# ramanSpectrometer_electronic_controlBoar.net
KiCad netlist of a schematic drawn in EAGLE
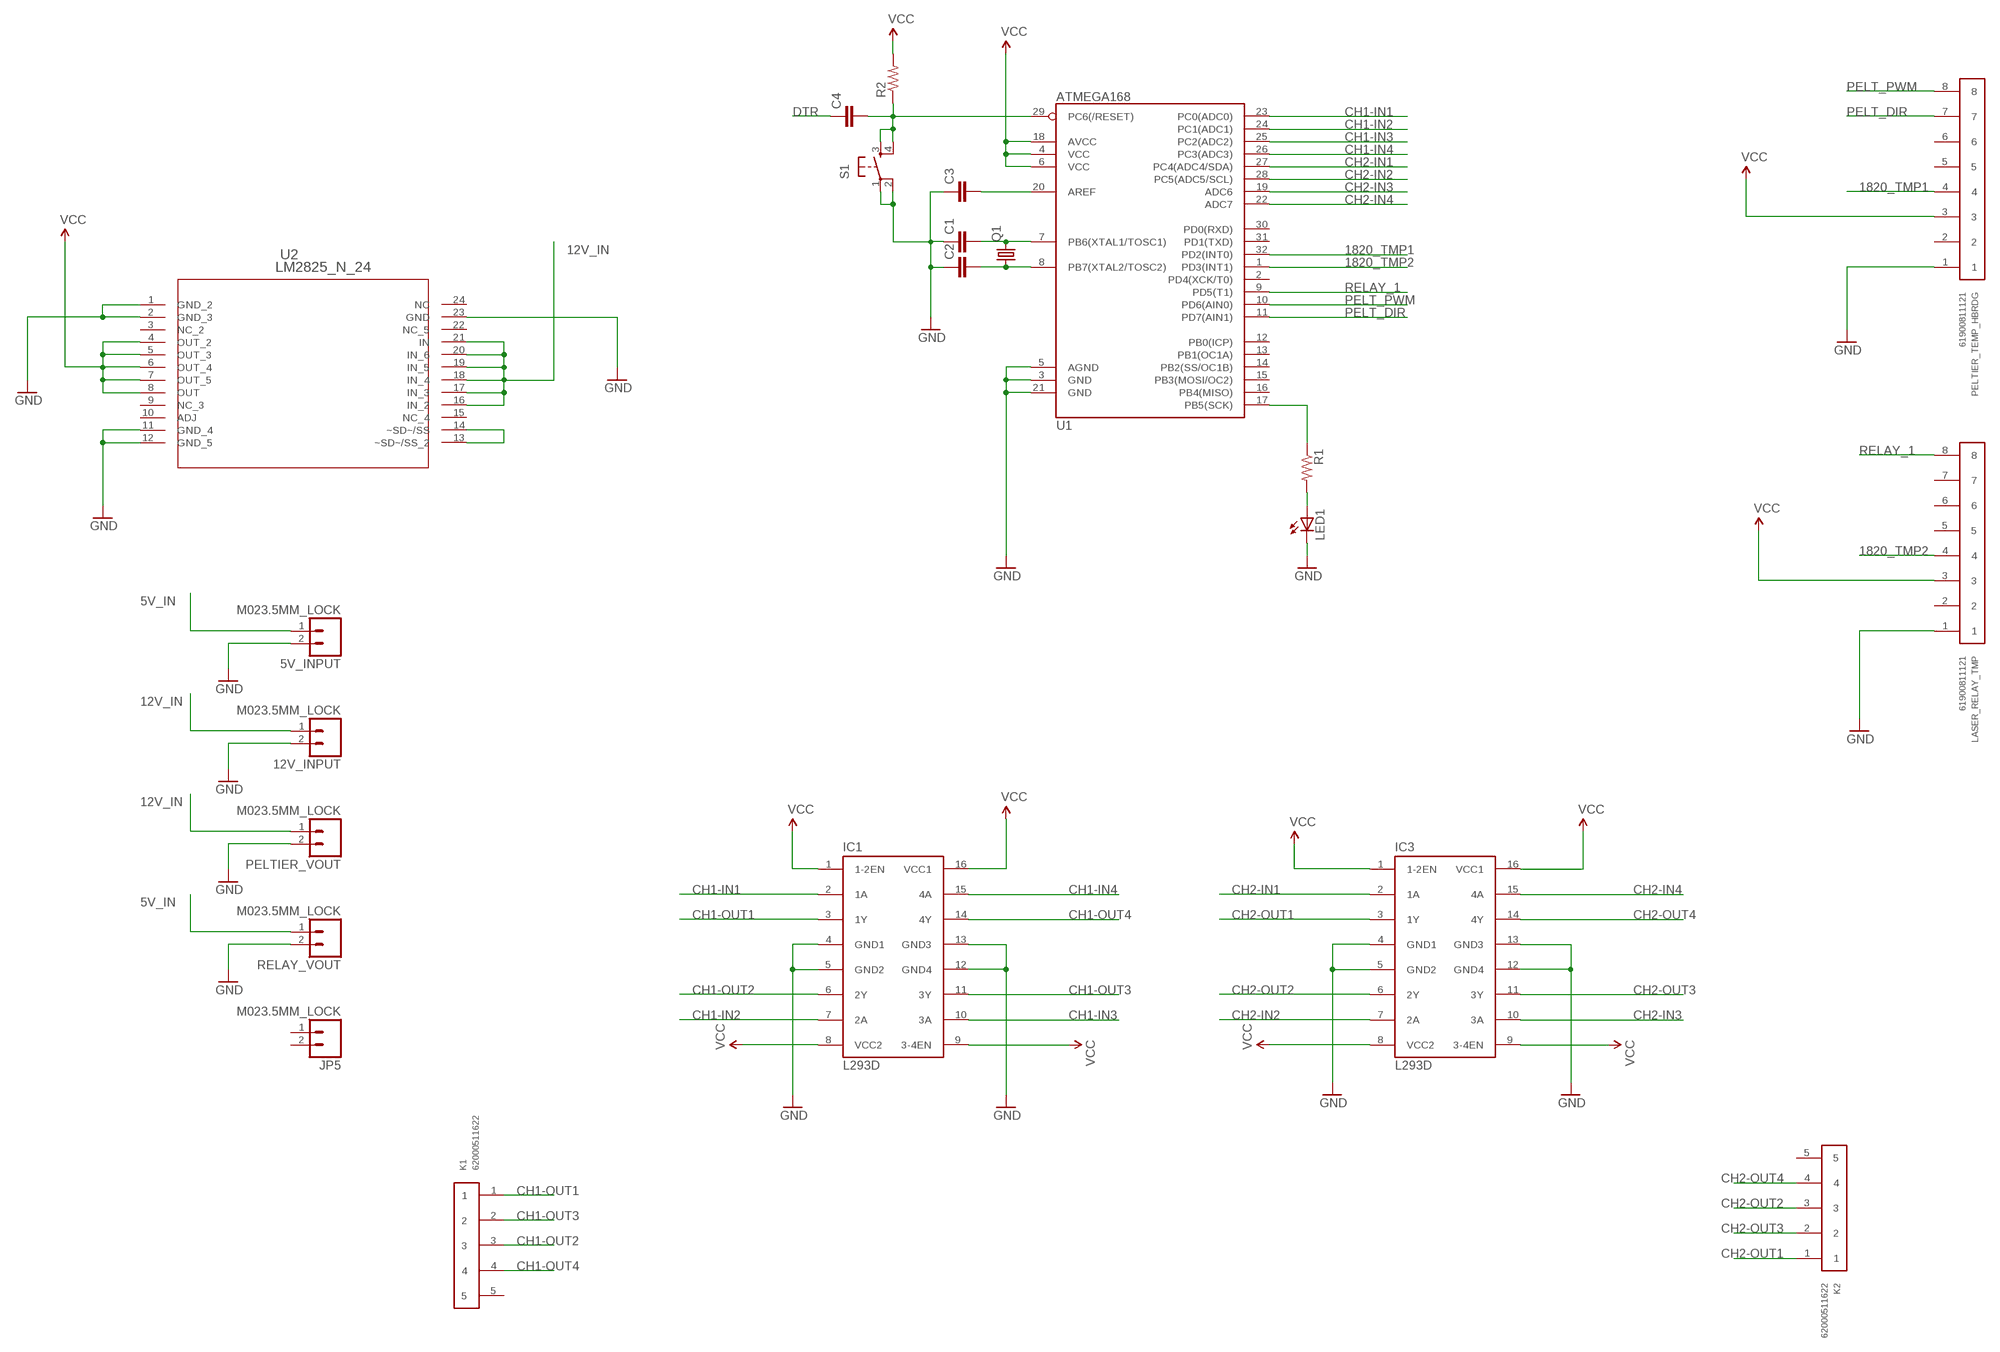
[diagram p0: schematic, sheet 1]

(export (version "E")
  (design (tool "Eeschema 10.0.6"))
  (components
    (comp (ref "5V_INPUT")
      (value "M023.5MM_LOCK")
      (footprint "eagle-import:SCREWTERMINAL-3.5MM-2_LOCK")
      (libsource (lib "eagle-import") (part "M023.5MM_LOCK"))
    )
    (comp (ref "12V_INPUT")
      (value "M023.5MM_LOCK")
      (footprint "eagle-import:SCREWTERMINAL-3.5MM-2_LOCK")
      (libsource (lib "eagle-import") (part "M023.5MM_LOCK"))
    )
    (comp (ref "C1")
      (value "CAP1206")
      (footprint "eagle-import:1206")
      (libsource (lib "eagle-import") (part "CAP1206"))
    )
    (comp (ref "C2")
      (value "CAP1206")
      (footprint "eagle-import:1206")
      (libsource (lib "eagle-import") (part "CAP1206"))
    )
    (comp (ref "C3")
      (value "CAP1210")
      (footprint "eagle-import:1210")
      (libsource (lib "eagle-import") (part "CAP1210"))
    )
    (comp (ref "C4")
      (value "CAP1210")
      (footprint "eagle-import:1210")
      (libsource (lib "eagle-import") (part "CAP1210"))
    )
    (comp (ref "IC1")
      (value "L293D")
      (footprint "eagle-import:DIL16")
      (libsource (lib "eagle-import") (part "L293D"))
    )
    (comp (ref "IC3")
      (value "L293D")
      (footprint "eagle-import:DIL16")
      (libsource (lib "eagle-import") (part "L293D"))
    )
    (comp (ref "JP5")
      (value "M023.5MM_LOCK")
      (footprint "eagle-import:SCREWTERMINAL-3.5MM-2_LOCK")
      (libsource (lib "eagle-import") (part "M023.5MM_LOCK"))
    )
    (comp (ref "K1")
      (value "62000511622")
      (footprint "eagle-import:62000511622")
      (libsource (lib "eagle-import") (part "62000511622"))
    )
    (comp (ref "K2")
      (value "62000511622")
      (footprint "eagle-import:62000511622")
      (libsource (lib "eagle-import") (part "62000511622"))
    )
    (comp (ref "LASER_RELAY_TMP")
      (value "61900811121")
      (footprint "eagle-import:61900811121")
      (libsource (lib "eagle-import") (part "61900811121"))
    )
    (comp (ref "LED1")
      (value "LEDP-LCC-2")
      (footprint "eagle-import:P-LCC-2")
      (libsource (lib "eagle-import") (part "LEDP-LCC-2"))
    )
    (comp (ref "PELTIER_TEMP_HBRDG")
      (value "61900811121")
      (footprint "eagle-import:61900811121")
      (libsource (lib "eagle-import") (part "61900811121"))
    )
    (comp (ref "PELTIER_VOUT")
      (value "M023.5MM_LOCK")
      (footprint "eagle-import:SCREWTERMINAL-3.5MM-2_LOCK")
      (libsource (lib "eagle-import") (part "M023.5MM_LOCK"))
    )
    (comp (ref "Q1")
      (value "CRYSTALSM49")
      (footprint "eagle-import:SM49")
      (libsource (lib "eagle-import") (part "CRYSTALSM49"))
    )
    (comp (ref "R1")
      (value "RESISTOR1206")
      (footprint "eagle-import:1206")
      (libsource (lib "eagle-import") (part "RESISTOR1206"))
    )
    (comp (ref "R2")
      (value "RESISTOR1206")
      (footprint "eagle-import:1206")
      (libsource (lib "eagle-import") (part "RESISTOR1206"))
    )
    (comp (ref "RELAY_VOUT")
      (value "M023.5MM_LOCK")
      (footprint "eagle-import:SCREWTERMINAL-3.5MM-2_LOCK")
      (libsource (lib "eagle-import") (part "M023.5MM_LOCK"))
    )
    (comp (ref "S1")
      (value "TAC_SWITCHSMD")
      (footprint "eagle-import:TACTILE_SWITCH_SMD")
      (libsource (lib "eagle-import") (part "TAC_SWITCHSMD"))
    )
    (comp (ref "U1")
      (value "ATMEGA168")
      (footprint "eagle-import:TQFP32-08")
      (libsource (lib "eagle-import") (part "ATMEGA168"))
    )
    (comp (ref "U2")
      (value "LM2825_N_24")
      (footprint "eagle-import:NA24F")
      (fields (field (name "PARTNUMBER") "LM2825HN-ADJ"))
      (libsource (lib "eagle-import") (part "LM2825_N_24"))
    )
  )
  (nets
    (net (code "1") (name "/5V_IN") (class "Default")
      (node (ref "5V_INPUT") (pin "1") (pinfunction "1_1") (pintype "passive"))
      (node (ref "RELAY_VOUT") (pin "1") (pinfunction "1_1") (pintype "passive"))
    )
    (net (code "2") (name "/12V_IN") (class "Default")
      (node (ref "12V_INPUT") (pin "1") (pinfunction "1_1") (pintype "passive"))
      (node (ref "PELTIER_VOUT") (pin "1") (pinfunction "1_1") (pintype "passive"))
      (node (ref "U2") (pin "16") (pinfunction "IN_2_16") (pintype "input"))
      (node (ref "U2") (pin "17") (pinfunction "IN_3_17") (pintype "input"))
      (node (ref "U2") (pin "18") (pinfunction "IN_4_18") (pintype "input"))
      (node (ref "U2") (pin "19") (pinfunction "IN_5_19") (pintype "input"))
      (node (ref "U2") (pin "20") (pinfunction "IN_6_20") (pintype "input"))
      (node (ref "U2") (pin "21") (pinfunction "IN_21") (pintype "input"))
    )
    (net (code "3") (name "/1820_TMP1") (class "Default")
      (node (ref "PELTIER_TEMP_HBRDG") (pin "4") (pinfunction "4_4") (pintype "bidirectional"))
      (node (ref "U1") (pin "32") (pinfunction "PD2(INT0)_32") (pintype "bidirectional"))
    )
    (net (code "4") (name "/1820_TMP2") (class "Default")
      (node (ref "LASER_RELAY_TMP") (pin "4") (pinfunction "4_4") (pintype "bidirectional"))
      (node (ref "U1") (pin "1") (pinfunction "PD3(INT1)_1") (pintype "bidirectional"))
    )
    (net (code "5") (name "/CH1-IN1") (class "Default")
      (node (ref "IC1") (pin "2") (pinfunction "1A_2") (pintype "input"))
      (node (ref "U1") (pin "23") (pinfunction "PC0(ADC0)_23") (pintype "bidirectional"))
    )
    (net (code "6") (name "/CH1-IN2") (class "Default")
      (node (ref "IC1") (pin "7") (pinfunction "2A_7") (pintype "input"))
      (node (ref "U1") (pin "24") (pinfunction "PC1(ADC1)_24") (pintype "bidirectional"))
    )
    (net (code "7") (name "/CH1-IN3") (class "Default")
      (node (ref "IC1") (pin "10") (pinfunction "3A_10") (pintype "input"))
      (node (ref "U1") (pin "25") (pinfunction "PC2(ADC2)_25") (pintype "bidirectional"))
    )
    (net (code "8") (name "/CH1-IN4") (class "Default")
      (node (ref "IC1") (pin "15") (pinfunction "4A_15") (pintype "input"))
      (node (ref "U1") (pin "26") (pinfunction "PC3(ADC3)_26") (pintype "bidirectional"))
    )
    (net (code "9") (name "/CH1-OUT1") (class "Default")
      (node (ref "IC1") (pin "3") (pinfunction "1Y_3") (pintype "output"))
      (node (ref "K1") (pin "1") (pinfunction "1_1") (pintype "bidirectional"))
    )
    (net (code "10") (name "/CH1-OUT2") (class "Default")
      (node (ref "IC1") (pin "6") (pinfunction "2Y_6") (pintype "output"))
      (node (ref "K1") (pin "3") (pinfunction "3_3") (pintype "bidirectional"))
    )
    (net (code "11") (name "/CH1-OUT3") (class "Default")
      (node (ref "IC1") (pin "11") (pinfunction "3Y_11") (pintype "output"))
      (node (ref "K1") (pin "2") (pinfunction "2_2") (pintype "bidirectional"))
    )
    (net (code "12") (name "/CH1-OUT4") (class "Default")
      (node (ref "IC1") (pin "14") (pinfunction "4Y_14") (pintype "output"))
      (node (ref "K1") (pin "4") (pinfunction "4_4") (pintype "bidirectional"))
    )
    (net (code "13") (name "/CH2-IN1") (class "Default")
      (node (ref "IC3") (pin "2") (pinfunction "1A_2") (pintype "input"))
      (node (ref "U1") (pin "27") (pinfunction "PC4(ADC4/SDA)_27") (pintype "bidirectional"))
    )
    (net (code "14") (name "/CH2-IN2") (class "Default")
      (node (ref "IC3") (pin "7") (pinfunction "2A_7") (pintype "input"))
      (node (ref "U1") (pin "28") (pinfunction "PC5(ADC5/SCL)_28") (pintype "bidirectional"))
    )
    (net (code "15") (name "/CH2-IN3") (class "Default")
      (node (ref "IC3") (pin "10") (pinfunction "3A_10") (pintype "input"))
      (node (ref "U1") (pin "19") (pinfunction "ADC6_19") (pintype "bidirectional"))
    )
    (net (code "16") (name "/CH2-IN4") (class "Default")
      (node (ref "IC3") (pin "15") (pinfunction "4A_15") (pintype "input"))
      (node (ref "U1") (pin "22") (pinfunction "ADC7_22") (pintype "bidirectional"))
    )
    (net (code "17") (name "/CH2-OUT1") (class "Default")
      (node (ref "IC3") (pin "3") (pinfunction "1Y_3") (pintype "output"))
      (node (ref "K2") (pin "1") (pinfunction "1_1") (pintype "bidirectional"))
    )
    (net (code "18") (name "/CH2-OUT2") (class "Default")
      (node (ref "IC3") (pin "6") (pinfunction "2Y_6") (pintype "output"))
      (node (ref "K2") (pin "3") (pinfunction "3_3") (pintype "bidirectional"))
    )
    (net (code "19") (name "/CH2-OUT3") (class "Default")
      (node (ref "IC3") (pin "11") (pinfunction "3Y_11") (pintype "output"))
      (node (ref "K2") (pin "2") (pinfunction "2_2") (pintype "bidirectional"))
    )
    (net (code "20") (name "/CH2-OUT4") (class "Default")
      (node (ref "IC3") (pin "14") (pinfunction "4Y_14") (pintype "output"))
      (node (ref "K2") (pin "4") (pinfunction "4_4") (pintype "bidirectional"))
    )
    (net (code "21") (name "/DTR") (class "Default")
      (node (ref "C4") (pin "1") (pinfunction "1_1") (pintype "passive"))
    )
    (net (code "22") (name "/PELT_DIR") (class "Default")
      (node (ref "PELTIER_TEMP_HBRDG") (pin "7") (pinfunction "7_7") (pintype "bidirectional"))
      (node (ref "U1") (pin "11") (pinfunction "PD7(AIN1)_11") (pintype "bidirectional"))
    )
    (net (code "23") (name "/PELT_PWM") (class "Default")
      (node (ref "PELTIER_TEMP_HBRDG") (pin "8") (pinfunction "8_8") (pintype "bidirectional"))
      (node (ref "U1") (pin "10") (pinfunction "PD6(AIN0)_10") (pintype "bidirectional"))
    )
    (net (code "24") (name "/RELAY_1") (class "Default")
      (node (ref "LASER_RELAY_TMP") (pin "8") (pinfunction "8_8") (pintype "bidirectional"))
      (node (ref "U1") (pin "9") (pinfunction "PD5(T1)_9") (pintype "bidirectional"))
    )
    (net (code "25") (name "GND") (class "Default")
      (node (ref "12V_INPUT") (pin "2") (pinfunction "2_2") (pintype "passive"))
      (node (ref "5V_INPUT") (pin "2") (pinfunction "2_2") (pintype "passive"))
      (node (ref "C1") (pin "1") (pinfunction "1_1") (pintype "passive"))
      (node (ref "C2") (pin "1") (pinfunction "1_1") (pintype "passive"))
      (node (ref "C3") (pin "1") (pinfunction "1_1") (pintype "passive"))
      (node (ref "IC1") (pin "12") (pinfunction "GND4_12") (pintype "power_in"))
      (node (ref "IC1") (pin "13") (pinfunction "GND3_13") (pintype "power_in"))
      (node (ref "IC1") (pin "4") (pinfunction "GND1_4") (pintype "power_in"))
      (node (ref "IC1") (pin "5") (pinfunction "GND2_5") (pintype "power_in"))
      (node (ref "IC3") (pin "12") (pinfunction "GND4_12") (pintype "power_in"))
      (node (ref "IC3") (pin "13") (pinfunction "GND3_13") (pintype "power_in"))
      (node (ref "IC3") (pin "4") (pinfunction "GND1_4") (pintype "power_in"))
      (node (ref "IC3") (pin "5") (pinfunction "GND2_5") (pintype "power_in"))
      (node (ref "LASER_RELAY_TMP") (pin "1") (pinfunction "1_1") (pintype "bidirectional"))
      (node (ref "LED1") (pin "C") (pinfunction "C_C") (pintype "passive"))
      (node (ref "PELTIER_TEMP_HBRDG") (pin "1") (pinfunction "1_1") (pintype "bidirectional"))
      (node (ref "PELTIER_VOUT") (pin "2") (pinfunction "2_2") (pintype "passive"))
      (node (ref "RELAY_VOUT") (pin "2") (pinfunction "2_2") (pintype "passive"))
      (node (ref "S1") (pin "1") (pinfunction "1_1") (pintype "passive"))
      (node (ref "S1") (pin "2") (pinfunction "2_2") (pintype "passive"))
      (node (ref "U1") (pin "21") (pinfunction "GND_21") (pintype "bidirectional"))
      (node (ref "U1") (pin "3") (pinfunction "GND_3") (pintype "bidirectional"))
      (node (ref "U1") (pin "5") (pinfunction "AGND_5") (pintype "bidirectional"))
      (node (ref "U2") (pin "1") (pinfunction "GND_2_1") (pintype "passive"))
      (node (ref "U2") (pin "11") (pinfunction "GND_4_11") (pintype "passive"))
      (node (ref "U2") (pin "12") (pinfunction "GND_5_12") (pintype "passive"))
      (node (ref "U2") (pin "2") (pinfunction "GND_3_2") (pintype "passive"))
      (node (ref "U2") (pin "23") (pinfunction "GND_23") (pintype "passive"))
    )
    (net (code "26") (name "Net-(LED1-PadA)") (class "Default")
      (node (ref "LED1") (pin "A") (pinfunction "A_A") (pintype "passive"))
      (node (ref "R1") (pin "2") (pinfunction "2_2") (pintype "passive"))
    )
    (net (code "27") (name "Net-(U1-AREF)") (class "Default")
      (node (ref "C3") (pin "2") (pinfunction "2_2") (pintype "passive"))
      (node (ref "U1") (pin "20") (pinfunction "AREF_20") (pintype "bidirectional"))
    )
    (net (code "28") (name "Net-(U1-PB5(SCK))") (class "Default")
      (node (ref "R1") (pin "1") (pinfunction "1_1") (pintype "passive"))
      (node (ref "U1") (pin "17") (pinfunction "PB5(SCK)_17") (pintype "bidirectional"))
    )
    (net (code "29") (name "Net-(U1-PB6(XTAL1{slash}TOSC1))") (class "Default")
      (node (ref "C1") (pin "2") (pinfunction "2_2") (pintype "passive"))
      (node (ref "Q1") (pin "2") (pinfunction "2_2") (pintype "passive"))
      (node (ref "U1") (pin "7") (pinfunction "PB6(XTAL1/TOSC1)_7") (pintype "bidirectional"))
    )
    (net (code "30") (name "Net-(U1-PB7(XTAL2{slash}TOSC2))") (class "Default")
      (node (ref "C2") (pin "2") (pinfunction "2_2") (pintype "passive"))
      (node (ref "Q1") (pin "1") (pinfunction "1_1") (pintype "passive"))
      (node (ref "U1") (pin "8") (pinfunction "PB7(XTAL2/TOSC2)_8") (pintype "bidirectional"))
    )
    (net (code "31") (name "Net-(U1-PC6({slash}RESET))") (class "Default")
      (node (ref "C4") (pin "2") (pinfunction "2_2") (pintype "passive"))
      (node (ref "R2") (pin "1") (pinfunction "1_1") (pintype "passive"))
      (node (ref "S1") (pin "3") (pinfunction "3_3") (pintype "passive"))
      (node (ref "S1") (pin "4") (pinfunction "4_4") (pintype "passive"))
      (node (ref "U1") (pin "29") (pinfunction "PC6(/RESET)_29") (pintype "bidirectional"))
    )
    (net (code "32") (name "Net-(U2-~{SD}{slash}SS)") (class "Default")
      (node (ref "U2") (pin "13") (pinfunction "~{SD}/SS_2_13") (pintype "passive"))
      (node (ref "U2") (pin "14") (pinfunction "~{SD}/SS_14") (pintype "passive"))
    )
    (net (code "33") (name "VCC") (class "Default")
      (node (ref "IC1") (pin "1") (pinfunction "1-2EN_1") (pintype "input"))
      (node (ref "IC1") (pin "16") (pinfunction "VCC1_16") (pintype "power_in"))
      (node (ref "IC1") (pin "8") (pinfunction "VCC2_8") (pintype "power_in"))
      (node (ref "IC1") (pin "9") (pinfunction "3-4EN_9") (pintype "input"))
      (node (ref "IC3") (pin "1") (pinfunction "1-2EN_1") (pintype "input"))
      (node (ref "IC3") (pin "16") (pinfunction "VCC1_16") (pintype "power_in"))
      (node (ref "IC3") (pin "8") (pinfunction "VCC2_8") (pintype "power_in"))
      (node (ref "IC3") (pin "9") (pinfunction "3-4EN_9") (pintype "input"))
      (node (ref "LASER_RELAY_TMP") (pin "3") (pinfunction "3_3") (pintype "bidirectional"))
      (node (ref "PELTIER_TEMP_HBRDG") (pin "3") (pinfunction "3_3") (pintype "bidirectional"))
      (node (ref "R2") (pin "2") (pinfunction "2_2") (pintype "passive"))
      (node (ref "U1") (pin "18") (pinfunction "AVCC_18") (pintype "bidirectional"))
      (node (ref "U1") (pin "4") (pinfunction "VCC_4") (pintype "bidirectional"))
      (node (ref "U1") (pin "6") (pinfunction "VCC_6") (pintype "bidirectional"))
      (node (ref "U2") (pin "4") (pinfunction "OUT_2_4") (pintype "output"))
      (node (ref "U2") (pin "5") (pinfunction "OUT_3_5") (pintype "output"))
      (node (ref "U2") (pin "6") (pinfunction "OUT_4_6") (pintype "output"))
      (node (ref "U2") (pin "7") (pinfunction "OUT_5_7") (pintype "output"))
      (node (ref "U2") (pin "8") (pinfunction "OUT_8") (pintype "output"))
    )
    (net (code "34") (name "unconnected-(JP5-Pad1)") (class "Default")
      (node (ref "JP5") (pin "1") (pinfunction "1_1") (pintype "passive"))
    )
    (net (code "35") (name "unconnected-(JP5-Pad2)") (class "Default")
      (node (ref "JP5") (pin "2") (pinfunction "2_2") (pintype "passive"))
    )
    (net (code "36") (name "unconnected-(K1-Pad5)") (class "Default")
      (node (ref "K1") (pin "5") (pinfunction "5_5") (pintype "bidirectional"))
    )
    (net (code "37") (name "unconnected-(K2-Pad5)") (class "Default")
      (node (ref "K2") (pin "5") (pinfunction "5_5") (pintype "bidirectional"))
    )
    (net (code "38") (name "unconnected-(LASER_RELAY_TMP-Pad2)") (class "Default")
      (node (ref "LASER_RELAY_TMP") (pin "2") (pinfunction "2_2") (pintype "bidirectional"))
    )
    (net (code "39") (name "unconnected-(LASER_RELAY_TMP-Pad5)") (class "Default")
      (node (ref "LASER_RELAY_TMP") (pin "5") (pinfunction "5_5") (pintype "bidirectional"))
    )
    (net (code "40") (name "unconnected-(LASER_RELAY_TMP-Pad6)") (class "Default")
      (node (ref "LASER_RELAY_TMP") (pin "6") (pinfunction "6_6") (pintype "bidirectional"))
    )
    (net (code "41") (name "unconnected-(LASER_RELAY_TMP-Pad7)") (class "Default")
      (node (ref "LASER_RELAY_TMP") (pin "7") (pinfunction "7_7") (pintype "bidirectional"))
    )
    (net (code "42") (name "unconnected-(PELTIER_TEMP_HBRDG-Pad2)") (class "Default")
      (node (ref "PELTIER_TEMP_HBRDG") (pin "2") (pinfunction "2_2") (pintype "bidirectional"))
    )
    (net (code "43") (name "unconnected-(PELTIER_TEMP_HBRDG-Pad5)") (class "Default")
      (node (ref "PELTIER_TEMP_HBRDG") (pin "5") (pinfunction "5_5") (pintype "bidirectional"))
    )
    (net (code "44") (name "unconnected-(PELTIER_TEMP_HBRDG-Pad6)") (class "Default")
      (node (ref "PELTIER_TEMP_HBRDG") (pin "6") (pinfunction "6_6") (pintype "bidirectional"))
    )
    (net (code "45") (name "unconnected-(U1-PB0(ICP)-Pad12)") (class "Default")
      (node (ref "U1") (pin "12") (pinfunction "PB0(ICP)_12") (pintype "bidirectional"))
    )
    (net (code "46") (name "unconnected-(U1-PB1(OC1A)-Pad13)") (class "Default")
      (node (ref "U1") (pin "13") (pinfunction "PB1(OC1A)_13") (pintype "bidirectional"))
    )
    (net (code "47") (name "unconnected-(U1-PB2(SS{slash}OC1B)-Pad14)") (class "Default")
      (node (ref "U1") (pin "14") (pinfunction "PB2(SS/OC1B)_14") (pintype "bidirectional"))
    )
    (net (code "48") (name "unconnected-(U1-PB3(MOSI{slash}OC2)-Pad15)") (class "Default")
      (node (ref "U1") (pin "15") (pinfunction "PB3(MOSI/OC2)_15") (pintype "bidirectional"))
    )
    (net (code "49") (name "unconnected-(U1-PB4(MISO)-Pad16)") (class "Default")
      (node (ref "U1") (pin "16") (pinfunction "PB4(MISO)_16") (pintype "bidirectional"))
    )
    (net (code "50") (name "unconnected-(U1-PD0(RXD)-Pad30)") (class "Default")
      (node (ref "U1") (pin "30") (pinfunction "PD0(RXD)_30") (pintype "bidirectional"))
    )
    (net (code "51") (name "unconnected-(U1-PD1(TXD)-Pad31)") (class "Default")
      (node (ref "U1") (pin "31") (pinfunction "PD1(TXD)_31") (pintype "bidirectional"))
    )
    (net (code "52") (name "unconnected-(U1-PD4(XCK{slash}T0)-Pad2)") (class "Default")
      (node (ref "U1") (pin "2") (pinfunction "PD4(XCK/T0)_2") (pintype "bidirectional"))
    )
    (net (code "53") (name "unconnected-(U2-ADJ-Pad10)") (class "Default")
      (node (ref "U2") (pin "10") (pinfunction "ADJ_10") (pintype "passive"))
    )
    (net (code "54") (name "unconnected-(U2-NC-Pad24)") (class "Default")
      (node (ref "U2") (pin "24") (pinfunction "NC_24") (pintype "passive"))
    )
    (net (code "55") (name "unconnected-(U2-NC_2-Pad3)") (class "Default")
      (node (ref "U2") (pin "3") (pinfunction "NC_2_3") (pintype "passive"))
    )
    (net (code "56") (name "unconnected-(U2-NC_3-Pad9)") (class "Default")
      (node (ref "U2") (pin "9") (pinfunction "NC_3_9") (pintype "passive"))
    )
    (net (code "57") (name "unconnected-(U2-NC_4-Pad15)") (class "Default")
      (node (ref "U2") (pin "15") (pinfunction "NC_4_15") (pintype "passive"))
    )
    (net (code "58") (name "unconnected-(U2-NC_5-Pad22)") (class "Default")
      (node (ref "U2") (pin "22") (pinfunction "NC_5_22") (pintype "passive"))
    )
  )
)
